# flight.net
KiCad netlist of a schematic drawn in EAGLE
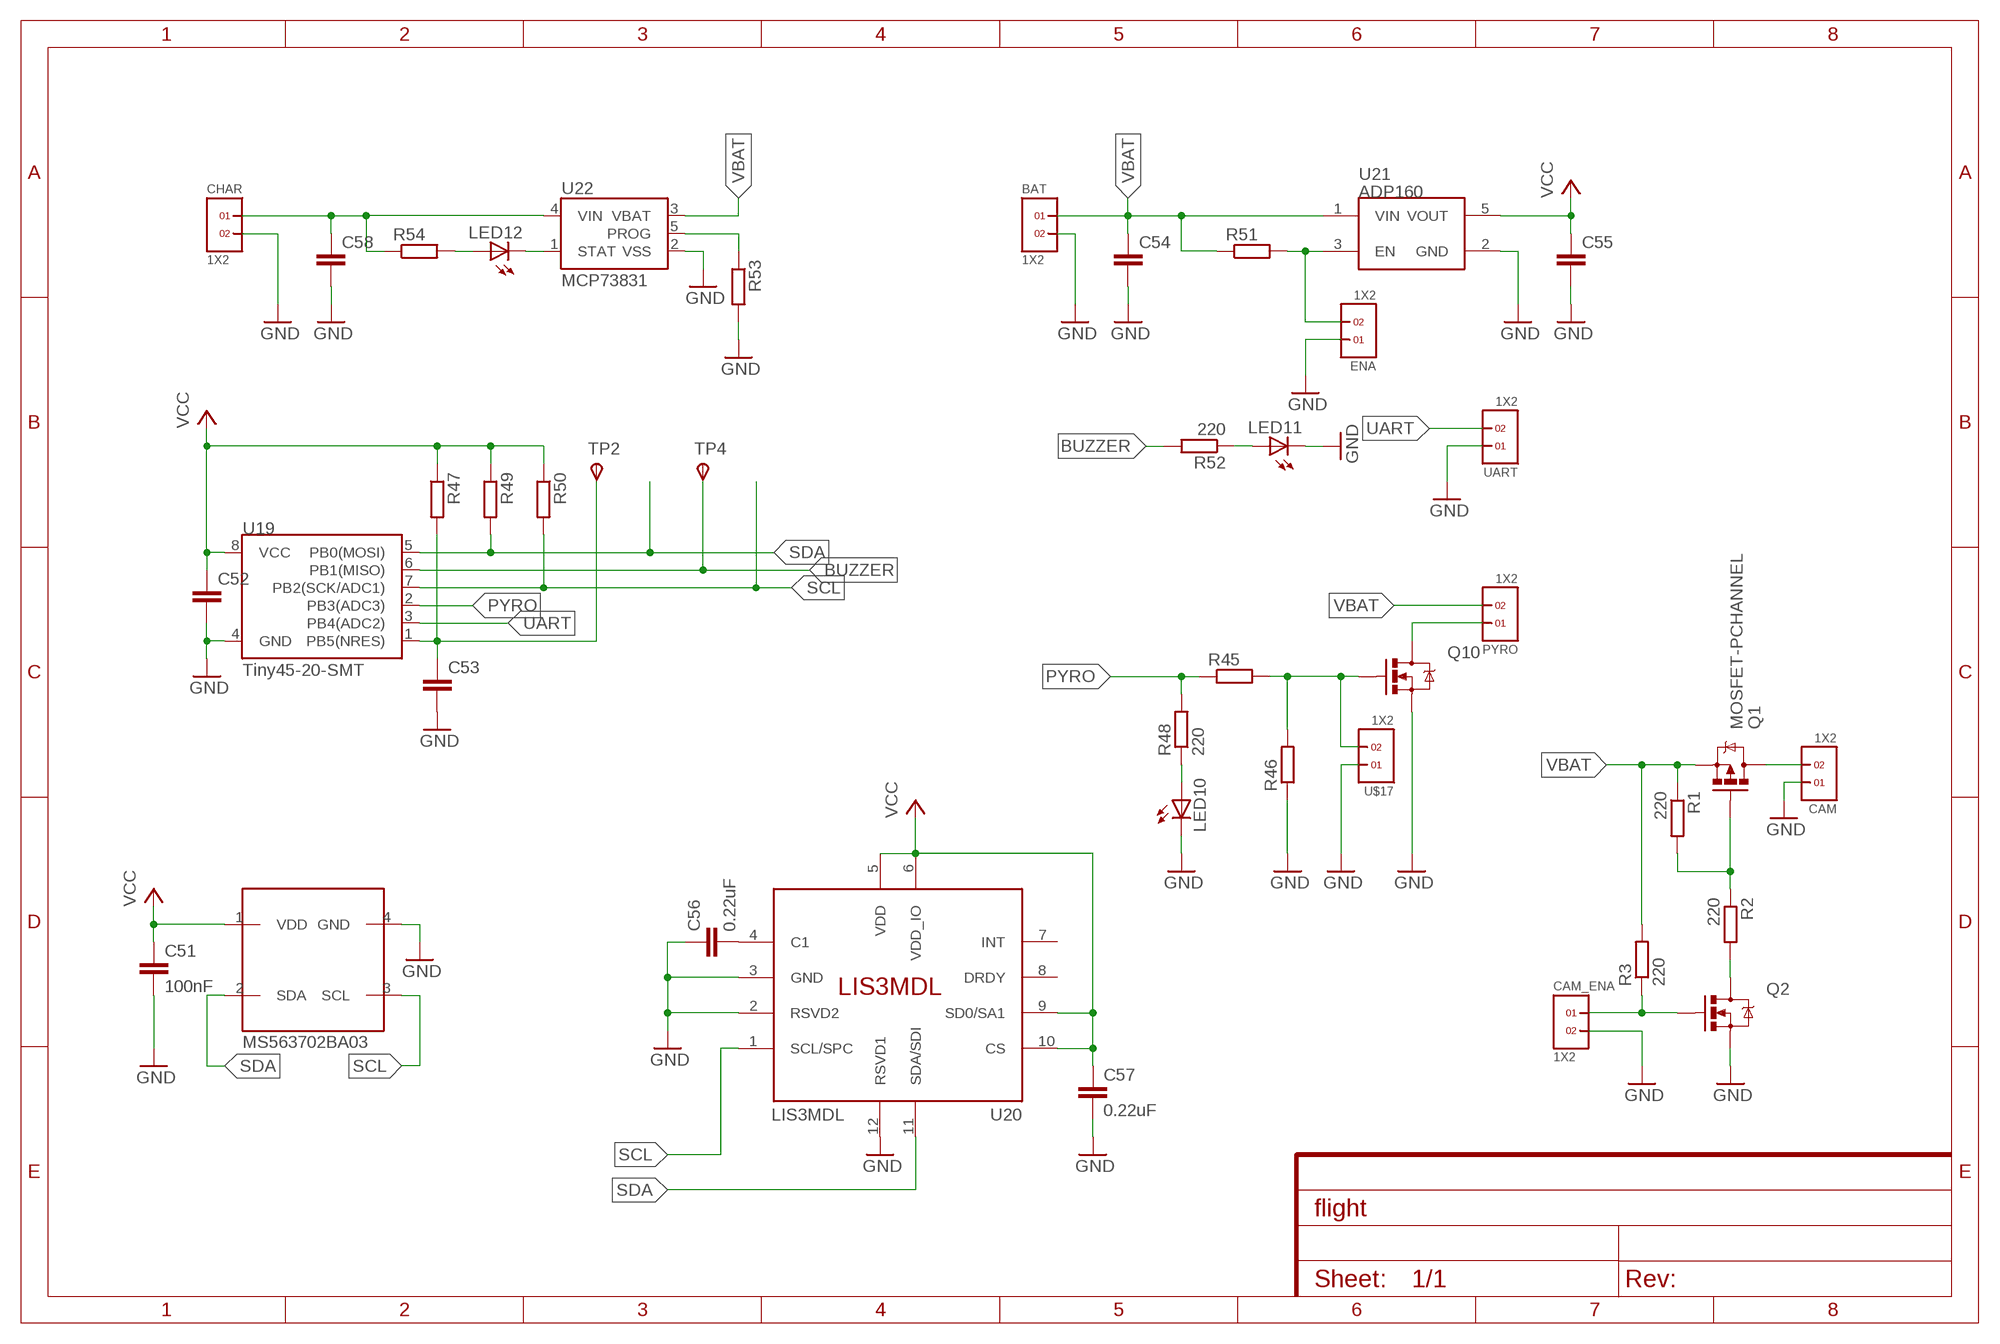
[diagram p0: schematic, sheet 1]

(export (version "E")
  (design (tool "Eeschema 10.0.6"))
  (components
    (comp (ref "BAT")
      (value "1X2")
      (footprint "eagle-import:1X2")
      (libsource (lib "eagle-import") (part "1X2"))
    )
    (comp (ref "C51")
      (value "100nF")
      (footprint "eagle-import:C0603")
      (libsource (lib "eagle-import") (part "C-EUC0603"))
    )
    (comp (ref "C52")
      (value "C-EUC1206")
      (footprint "eagle-import:C1206")
      (libsource (lib "eagle-import") (part "C-EUC1206"))
    )
    (comp (ref "C53")
      (value "C-EUC0603")
      (footprint "eagle-import:C0603")
      (libsource (lib "eagle-import") (part "C-EUC0603"))
    )
    (comp (ref "C54")
      (value "C-EUC0603")
      (footprint "eagle-import:C0603")
      (libsource (lib "eagle-import") (part "C-EUC0603"))
    )
    (comp (ref "C55")
      (value "C-EUC0603")
      (footprint "eagle-import:C0603")
      (libsource (lib "eagle-import") (part "C-EUC0603"))
    )
    (comp (ref "C56")
      (value "0.22uF")
      (footprint "eagle-import:C0603K")
      (libsource (lib "eagle-import") (part "C-EUC0603K"))
    )
    (comp (ref "C57")
      (value "0.22uF")
      (footprint "eagle-import:C0603")
      (libsource (lib "eagle-import") (part "C-EUC0603"))
    )
    (comp (ref "C58")
      (value "C-EUC0603")
      (footprint "eagle-import:C0603")
      (libsource (lib "eagle-import") (part "C-EUC0603"))
    )
    (comp (ref "CAM")
      (value "1X2")
      (footprint "eagle-import:1X2")
      (libsource (lib "eagle-import") (part "1X2"))
    )
    (comp (ref "CAM_ENA")
      (value "1X2")
      (footprint "eagle-import:1X2")
      (libsource (lib "eagle-import") (part "1X2"))
    )
    (comp (ref "CHAR")
      (value "1X2")
      (footprint "eagle-import:1X2")
      (libsource (lib "eagle-import") (part "1X2"))
    )
    (comp (ref "ENA")
      (value "1X2")
      (footprint "eagle-import:1X2")
      (libsource (lib "eagle-import") (part "1X2"))
    )
    (comp (ref "IC2")
      (value "MS563702BA03")
      (footprint "eagle-import:MS5637")
      (libsource (lib "eagle-import") (part "MS563702BA03"))
    )
    (comp (ref "LED10")
      (value "LEDCHIPLED_0805")
      (footprint "eagle-import:CHIPLED_0805")
      (libsource (lib "eagle-import") (part "LEDCHIPLED_0805"))
    )
    (comp (ref "LED11")
      (value "LEDCHIPLED_0805")
      (footprint "eagle-import:CHIPLED_0805")
      (libsource (lib "eagle-import") (part "LEDCHIPLED_0805"))
    )
    (comp (ref "LED12")
      (value "LEDCHIPLED_0603")
      (footprint "eagle-import:CHIPLED_0603")
      (libsource (lib "eagle-import") (part "LEDCHIPLED_0603"))
    )
    (comp (ref "PYRO")
      (value "1X2")
      (footprint "eagle-import:1X2")
      (libsource (lib "eagle-import") (part "1X2"))
    )
    (comp (ref "Q1")
      (value "MOSFET-PCHANNEL")
      (footprint "eagle-import:SOT23-3")
      (libsource (lib "eagle-import") (part "MOSFET-PCHANNEL"))
    )
    (comp (ref "Q2")
      (value "MOSFET-NCHANNELBSS123LT1G")
      (footprint "eagle-import:SOT23-3")
      (libsource (lib "eagle-import") (part "MOSFET-NCHANNELBSS123LT1G"))
    )
    (comp (ref "Q10")
      (value "MOSFET-NCHANNELBSS123LT1G")
      (footprint "eagle-import:SOT23-3")
      (libsource (lib "eagle-import") (part "MOSFET-NCHANNELBSS123LT1G"))
    )
    (comp (ref "R1")
      (value "220")
      (footprint "eagle-import:R0603")
      (libsource (lib "eagle-import") (part "resistor_R-EU_R0603"))
    )
    (comp (ref "R2")
      (value "220")
      (footprint "eagle-import:R0603")
      (libsource (lib "eagle-import") (part "resistor_R-EU_R0603"))
    )
    (comp (ref "R3")
      (value "220")
      (footprint "eagle-import:R0603")
      (libsource (lib "eagle-import") (part "resistor_R-EU_R0603"))
    )
    (comp (ref "R45")
      (value "R-EU_R0603")
      (footprint "eagle-import:R0603")
      (libsource (lib "eagle-import") (part "R-EU_R0603"))
    )
    (comp (ref "R46")
      (value "R-EU_R0603")
      (footprint "eagle-import:R0603")
      (libsource (lib "eagle-import") (part "R-EU_R0603"))
    )
    (comp (ref "R47")
      (value "R-EU_R0603")
      (footprint "eagle-import:R0603")
      (libsource (lib "eagle-import") (part "R-EU_R0603"))
    )
    (comp (ref "R48")
      (value "220")
      (footprint "eagle-import:R0603")
      (libsource (lib "eagle-import") (part "resistor_R-EU_R0603"))
    )
    (comp (ref "R49")
      (value "R-EU_R0603")
      (footprint "eagle-import:R0603")
      (libsource (lib "eagle-import") (part "R-EU_R0603"))
    )
    (comp (ref "R50")
      (value "R-EU_R0603")
      (footprint "eagle-import:R0603")
      (libsource (lib "eagle-import") (part "R-EU_R0603"))
    )
    (comp (ref "R51")
      (value "R-EU_R0603")
      (footprint "eagle-import:R0603")
      (libsource (lib "eagle-import") (part "R-EU_R0603"))
    )
    (comp (ref "R52")
      (value "220")
      (footprint "eagle-import:R0603")
      (libsource (lib "eagle-import") (part "resistor_R-EU_R0603"))
    )
    (comp (ref "R53")
      (value "R-EU_R0603")
      (footprint "eagle-import:R0603")
      (libsource (lib "eagle-import") (part "R-EU_R0603"))
    )
    (comp (ref "R54")
      (value "R-EU_R0603")
      (footprint "eagle-import:R0603")
      (libsource (lib "eagle-import") (part "R-EU_R0603"))
    )
    (comp (ref "TP2")
      (value "TPSB1,27")
      (footprint "eagle-import:B1,27")
      (libsource (lib "eagle-import") (part "TPSB1,27"))
    )
    (comp (ref "TP4")
      (value "TPSB1,27")
      (footprint "eagle-import:B1,27")
      (libsource (lib "eagle-import") (part "TPSB1,27"))
    )
    (comp (ref "U$17")
      (value "1X2")
      (footprint "eagle-import:1X2")
      (libsource (lib "eagle-import") (part "1X2"))
    )
    (comp (ref "U19")
      (value "Tiny45-20-SMT")
      (footprint "eagle-import:SO08-EIAJ")
      (libsource (lib "eagle-import") (part "ATTINY45TINY45-20-SMT"))
    )
    (comp (ref "U20")
      (value "LIS3MDL")
      (footprint "eagle-import:VFLGA-12")
      (libsource (lib "eagle-import") (part "LIS3MDL"))
    )
    (comp (ref "U21")
      (value "ADP160")
      (footprint "eagle-import:SOT23-5")
      (libsource (lib "eagle-import") (part "ADP160"))
    )
    (comp (ref "U22")
      (value "MCP73831")
      (footprint "eagle-import:SOT23-5")
      (libsource (lib "eagle-import") (part "MCP73831"))
    )
    (comp (ref "UART")
      (value "1X2")
      (footprint "eagle-import:1X2")
      (libsource (lib "eagle-import") (part "1X2"))
    )
  )
  (nets
    (net (code "1") (name "BUZZER") (class "Default")
      (node (ref "R52") (pin "2") (pinfunction "2_2") (pintype "passive"))
      (node (ref "TP4") (pin "TP") (pinfunction "PP_TP") (pintype "input"))
      (node (ref "U19") (pin "6") (pinfunction "PB1(MISO)_6") (pintype "bidirectional"))
    )
    (net (code "2") (name "GND") (class "Default")
      (node (ref "BAT") (pin "2") (pinfunction "2_2") (pintype "bidirectional"))
      (node (ref "C51") (pin "2") (pinfunction "2_2") (pintype "passive"))
      (node (ref "C52") (pin "2") (pinfunction "2_2") (pintype "passive"))
      (node (ref "C53") (pin "2") (pinfunction "2_2") (pintype "passive"))
      (node (ref "C54") (pin "2") (pinfunction "2_2") (pintype "passive"))
      (node (ref "C55") (pin "2") (pinfunction "2_2") (pintype "passive"))
      (node (ref "C56") (pin "1") (pinfunction "1_1") (pintype "passive"))
      (node (ref "C57") (pin "2") (pinfunction "2_2") (pintype "passive"))
      (node (ref "C58") (pin "2") (pinfunction "2_2") (pintype "passive"))
      (node (ref "CAM") (pin "1") (pinfunction "1_1") (pintype "bidirectional"))
      (node (ref "CAM_ENA") (pin "2") (pinfunction "2_2") (pintype "bidirectional"))
      (node (ref "CHAR") (pin "2") (pinfunction "2_2") (pintype "bidirectional"))
      (node (ref "ENA") (pin "1") (pinfunction "1_1") (pintype "bidirectional"))
      (node (ref "IC2") (pin "4") (pinfunction "GND_4") (pintype "bidirectional"))
      (node (ref "LED10") (pin "C") (pinfunction "C_C") (pintype "passive"))
      (node (ref "LED11") (pin "C") (pinfunction "C_C") (pintype "passive"))
      (node (ref "Q10") (pin "2") (pinfunction "S_2") (pintype "passive"))
      (node (ref "Q2") (pin "2") (pinfunction "S_2") (pintype "passive"))
      (node (ref "R46") (pin "1") (pinfunction "1_1") (pintype "passive"))
      (node (ref "R53") (pin "2") (pinfunction "2_2") (pintype "passive"))
      (node (ref "U$17") (pin "1") (pinfunction "1_1") (pintype "bidirectional"))
      (node (ref "U19") (pin "4") (pinfunction "GND_4") (pintype "bidirectional"))
      (node (ref "U20") (pin "12") (pinfunction "RSVD1_12") (pintype "bidirectional"))
      (node (ref "U20") (pin "2") (pinfunction "RSVD2_2") (pintype "bidirectional"))
      (node (ref "U20") (pin "3") (pinfunction "GND_3") (pintype "power_in"))
      (node (ref "U21") (pin "2") (pinfunction "GND_2") (pintype "bidirectional"))
      (node (ref "U22") (pin "2") (pinfunction "VSS_2") (pintype "power_in"))
      (node (ref "UART") (pin "1") (pinfunction "1_1") (pintype "bidirectional"))
    )
    (net (code "3") (name "Net-(LED10-PadA)") (class "Default")
      (node (ref "LED10") (pin "A") (pinfunction "A_A") (pintype "passive"))
      (node (ref "R48") (pin "1") (pinfunction "1_1") (pintype "passive"))
    )
    (net (code "4") (name "Net-(LED11-PadA)") (class "Default")
      (node (ref "LED11") (pin "A") (pinfunction "A_A") (pintype "passive"))
      (node (ref "R52") (pin "1") (pinfunction "1_1") (pintype "passive"))
    )
    (net (code "5") (name "Net-(LED12-PadA)") (class "Default")
      (node (ref "LED12") (pin "A") (pinfunction "A_A") (pintype "passive"))
      (node (ref "R54") (pin "2") (pinfunction "2_2") (pintype "passive"))
    )
    (net (code "6") (name "Net-(Q1-D)") (class "Default")
      (node (ref "CAM") (pin "2") (pinfunction "2_2") (pintype "bidirectional"))
      (node (ref "Q1") (pin "3") (pinfunction "D_3") (pintype "passive"))
    )
    (net (code "7") (name "Net-(Q1-G)") (class "Default")
      (node (ref "Q1") (pin "1") (pinfunction "G_1") (pintype "passive"))
      (node (ref "R1") (pin "2") (pinfunction "2_2") (pintype "passive"))
      (node (ref "R2") (pin "1") (pinfunction "1_1") (pintype "passive"))
    )
    (net (code "8") (name "Net-(Q2-D)") (class "Default")
      (node (ref "Q2") (pin "3") (pinfunction "D_3") (pintype "passive"))
      (node (ref "R2") (pin "2") (pinfunction "2_2") (pintype "passive"))
    )
    (net (code "9") (name "Net-(Q2-G)") (class "Default")
      (node (ref "CAM_ENA") (pin "1") (pinfunction "1_1") (pintype "bidirectional"))
      (node (ref "Q2") (pin "1") (pinfunction "G_1") (pintype "passive"))
      (node (ref "R3") (pin "1") (pinfunction "1_1") (pintype "passive"))
    )
    (net (code "10") (name "Net-(Q10-D)") (class "Default")
      (node (ref "PYRO") (pin "1") (pinfunction "1_1") (pintype "bidirectional"))
      (node (ref "Q10") (pin "3") (pinfunction "D_3") (pintype "passive"))
    )
    (net (code "11") (name "Net-(Q10-G)") (class "Default")
      (node (ref "Q10") (pin "1") (pinfunction "G_1") (pintype "passive"))
      (node (ref "R45") (pin "2") (pinfunction "2_2") (pintype "passive"))
      (node (ref "R46") (pin "2") (pinfunction "2_2") (pintype "passive"))
      (node (ref "U$17") (pin "2") (pinfunction "2_2") (pintype "bidirectional"))
    )
    (net (code "12") (name "Net-(TP2-PP)") (class "Default")
      (node (ref "C53") (pin "1") (pinfunction "1_1") (pintype "passive"))
      (node (ref "R47") (pin "2") (pinfunction "2_2") (pintype "passive"))
      (node (ref "TP2") (pin "TP") (pinfunction "PP_TP") (pintype "input"))
      (node (ref "U19") (pin "1") (pinfunction "PB5(NRES)_1") (pintype "bidirectional"))
    )
    (net (code "13") (name "Net-(U20-C1)") (class "Default")
      (node (ref "C56") (pin "2") (pinfunction "2_2") (pintype "passive"))
      (node (ref "U20") (pin "4") (pinfunction "C1_4") (pintype "bidirectional"))
    )
    (net (code "14") (name "Net-(U21-EN)") (class "Default")
      (node (ref "ENA") (pin "2") (pinfunction "2_2") (pintype "bidirectional"))
      (node (ref "R51") (pin "2") (pinfunction "2_2") (pintype "passive"))
      (node (ref "U21") (pin "3") (pinfunction "EN_3") (pintype "bidirectional"))
    )
    (net (code "15") (name "Net-(U22-PROG)") (class "Default")
      (node (ref "R53") (pin "1") (pinfunction "1_1") (pintype "passive"))
      (node (ref "U22") (pin "5") (pinfunction "PROG_5") (pintype "input"))
    )
    (net (code "16") (name "Net-(U22-STAT)") (class "Default")
      (node (ref "LED12") (pin "C") (pinfunction "C_C") (pintype "passive"))
      (node (ref "U22") (pin "1") (pinfunction "STAT_1") (pintype "output"))
    )
    (net (code "17") (name "Net-(U22-VIN)") (class "Default")
      (node (ref "C58") (pin "1") (pinfunction "1_1") (pintype "passive"))
      (node (ref "CHAR") (pin "1") (pinfunction "1_1") (pintype "bidirectional"))
      (node (ref "R54") (pin "1") (pinfunction "1_1") (pintype "passive"))
      (node (ref "U22") (pin "4") (pinfunction "VIN_4") (pintype "power_in"))
    )
    (net (code "18") (name "PYRO") (class "Default")
      (node (ref "R45") (pin "1") (pinfunction "1_1") (pintype "passive"))
      (node (ref "R48") (pin "2") (pinfunction "2_2") (pintype "passive"))
      (node (ref "U19") (pin "2") (pinfunction "PB3(ADC3)_2") (pintype "bidirectional"))
    )
    (net (code "19") (name "SCL") (class "Default")
      (node (ref "IC2") (pin "3") (pinfunction "SCL_3") (pintype "bidirectional"))
      (node (ref "R50") (pin "2") (pinfunction "2_2") (pintype "passive"))
      (node (ref "U19") (pin "7") (pinfunction "PB2(SCK/ADC1)_7") (pintype "bidirectional"))
      (node (ref "U20") (pin "1") (pinfunction "SCL/SPC_1") (pintype "bidirectional"))
    )
    (net (code "20") (name "SDA") (class "Default")
      (node (ref "IC2") (pin "2") (pinfunction "SDA_2") (pintype "bidirectional"))
      (node (ref "R49") (pin "2") (pinfunction "2_2") (pintype "passive"))
      (node (ref "U19") (pin "5") (pinfunction "PB0(MOSI)_5") (pintype "bidirectional"))
      (node (ref "U20") (pin "11") (pinfunction "SDA/SDI_11") (pintype "bidirectional"))
    )
    (net (code "21") (name "UART") (class "Default")
      (node (ref "U19") (pin "3") (pinfunction "PB4(ADC2)_3") (pintype "bidirectional"))
      (node (ref "UART") (pin "2") (pinfunction "2_2") (pintype "bidirectional"))
    )
    (net (code "22") (name "VBAT") (class "Default")
      (node (ref "BAT") (pin "1") (pinfunction "1_1") (pintype "bidirectional"))
      (node (ref "C54") (pin "1") (pinfunction "1_1") (pintype "passive"))
      (node (ref "PYRO") (pin "2") (pinfunction "2_2") (pintype "bidirectional"))
      (node (ref "Q1") (pin "2") (pinfunction "S_2") (pintype "passive"))
      (node (ref "R1") (pin "1") (pinfunction "1_1") (pintype "passive"))
      (node (ref "R3") (pin "2") (pinfunction "2_2") (pintype "passive"))
      (node (ref "R51") (pin "1") (pinfunction "1_1") (pintype "passive"))
      (node (ref "U21") (pin "1") (pinfunction "VIN_1") (pintype "bidirectional"))
      (node (ref "U22") (pin "3") (pinfunction "VBAT_3") (pintype "power_in"))
    )
    (net (code "23") (name "VCC") (class "Default")
      (node (ref "C51") (pin "1") (pinfunction "1_1") (pintype "passive"))
      (node (ref "C52") (pin "1") (pinfunction "1_1") (pintype "passive"))
      (node (ref "C55") (pin "1") (pinfunction "1_1") (pintype "passive"))
      (node (ref "C57") (pin "1") (pinfunction "1_1") (pintype "passive"))
      (node (ref "IC2") (pin "1") (pinfunction "VDD_1") (pintype "bidirectional"))
      (node (ref "R47") (pin "1") (pinfunction "1_1") (pintype "passive"))
      (node (ref "R49") (pin "1") (pinfunction "1_1") (pintype "passive"))
      (node (ref "R50") (pin "1") (pinfunction "1_1") (pintype "passive"))
      (node (ref "U19") (pin "8") (pinfunction "VCC_8") (pintype "bidirectional"))
      (node (ref "U20") (pin "10") (pinfunction "CS_10") (pintype "bidirectional"))
      (node (ref "U20") (pin "5") (pinfunction "VDD_5") (pintype "bidirectional"))
      (node (ref "U20") (pin "6") (pinfunction "VDD_IO_6") (pintype "power_in"))
      (node (ref "U20") (pin "9") (pinfunction "SD0/SA1_9") (pintype "bidirectional"))
      (node (ref "U21") (pin "5") (pinfunction "VOUT_5") (pintype "bidirectional"))
    )
    (net (code "24") (name "unconnected-(U20-DRDY-Pad8)") (class "Default")
      (node (ref "U20") (pin "8") (pinfunction "DRDY_8") (pintype "bidirectional"))
    )
    (net (code "25") (name "unconnected-(U20-INT-Pad7)") (class "Default")
      (node (ref "U20") (pin "7") (pinfunction "INT_7") (pintype "bidirectional"))
    )
  )
)
